# RF.net
KiCad netlist of a schematic drawn in Altium Designer
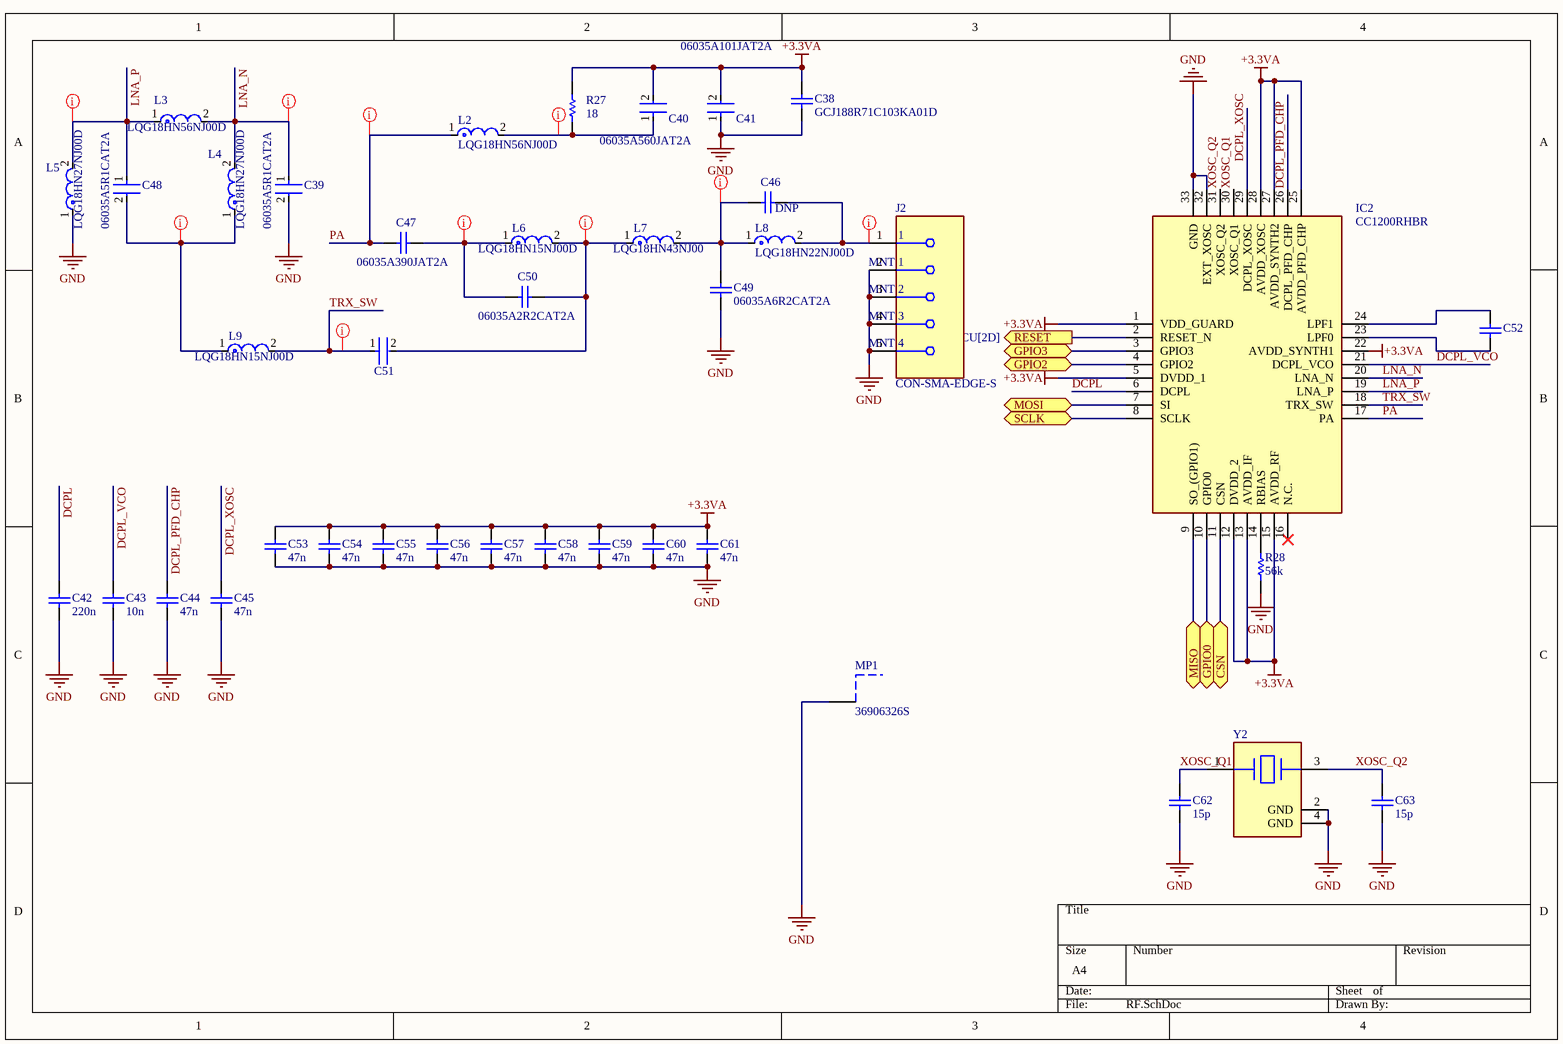
[diagram p0: RF.SchDoc]

(export (version "E")
  (design (tool "Eeschema 10.0.6"))
  (components
    (comp (ref "C38")
      (value "GCJ188R71C103KA01D")
      (footprint "CAPC1608X90X35LL10T15")
      (description "Cap Ceramic 0.01uF 16V X7R 10% Pad SMD 0603 Soft Termination 125C Automotive T/R")
      (fields (field (name "MANUFACTURER") "Murata"))
      (libsource (lib "Altium Content Vault") (part "CAP-NP-2"))
    )
    (comp (ref "C39")
      (value "06035A5R1CAT2A")
      (footprint "FP-GCM188-0_1-IPC_A")
      (description "0603 5.1 pF 50 V ±0.25 pF Tolerance C0G/NP0 Multilayer Ceramic Capacitor")
      (libsource (lib "Altium Content Vault") (part "02cd4be3c70576c341d710602a673aa"))
    )
    (comp (ref "C40")
      (value "06035A560JAT2A")
      (footprint "FP-GCM188-0_1-IPC_A")
      (description "0603 56 pF 50 V ±5% Tolerance C0G/NP0 Surface Mount Multilayer Ceramic Capacitor")
      (libsource (lib "Altium Content Vault") (part "02cd4be3c70576c341d710602a673aa"))
    )
    (comp (ref "C41")
      (value "06035A101JAT2A")
      (footprint "FP-GCM188-0_1-IPC_A")
      (description "0603 100 pF 50 V ±5% Tolerance C0G/NP0 SMT Multilayer Ceramic Capacitor")
      (libsource (lib "Altium Content Vault") (part "02cd4be3c70576c341d710602a673aa"))
    )
    (comp (ref "C42")
      (value "220n")
      (footprint "RES_0805")
      (description "Capacitor")
      (libsource (lib "Simulation Generic Components") (part "Capacitor"))
    )
    (comp (ref "C43")
      (value "10n")
      (footprint "RES_0805")
      (description "Capacitor")
      (libsource (lib "Simulation Generic Components") (part "Capacitor"))
    )
    (comp (ref "C44")
      (value "47n")
      (footprint "RES_0805")
      (description "Capacitor")
      (libsource (lib "Simulation Generic Components") (part "Capacitor"))
    )
    (comp (ref "C45")
      (value "47n")
      (footprint "RES_0805")
      (description "Capacitor")
      (libsource (lib "Simulation Generic Components") (part "Capacitor"))
    )
    (comp (ref "C46")
      (value "DNP")
      (footprint "CAPC1608X90X35LL15T15")
      (fields
        (field (name "PART NUMBER") "06035A6R2CAT2A")
        (field (name "MANUFACTURER") "AVX Interconnect / Elco")
      )
      (libsource (lib "Altium Content Vault") (part "CAP"))
    )
    (comp (ref "C47")
      (value "06035A390JAT2A")
      (footprint "CAPC1608X90X35LL15T15")
      (fields
        (field (name "PART NUMBER") "06035A6R2CAT2A")
        (field (name "MANUFACTURER") "AVX Interconnect / Elco")
      )
      (libsource (lib "Altium Content Vault") (part "CAP"))
    )
    (comp (ref "C48")
      (value "06035A5R1CAT2A")
      (footprint "FP-GCM188-0_1-IPC_A")
      (description "0603 5.1 pF 50 V ±0.25 pF Tolerance C0G/NP0 Multilayer Ceramic Capacitor")
      (libsource (lib "Altium Content Vault") (part "02cd4be3c70576c341d710602a673aa"))
    )
    (comp (ref "C49")
      (value "06035A6R2CAT2A")
      (footprint "CAPC1608X90X35LL15T15")
      (fields (field (name "MANUFACTURER") "AVX Interconnect / Elco"))
      (libsource (lib "Altium Content Vault") (part "CAP"))
    )
    (comp (ref "C50")
      (value "06035A2R2CAT2A")
      (footprint "CAPC1608X90X35LL15T15")
      (description "0603 2.2 pF 50 V ±0.25 pF Tolerance C0G/NP0 SMT Multilayer Ceramic Capacitor")
      (fields
        (field (name "PART NUMBER") "06035A6R2CAT2A")
        (field (name "MANUFACTURER") "AVX Interconnect / Elco")
      )
      (libsource (lib "Altium Content Vault") (part "CAP"))
    )
    (comp (ref "C51")
      (value "06035A5R1CAT2A")
      (footprint "FP-GCM188-0_1-IPC_A")
      (description "0603 5.1 pF 50 V ±0.25 pF Tolerance C0G/NP0 Multilayer Ceramic Capacitor")
      (libsource (lib "Altium Content Vault") (part "02cd4be3c70576c341d710602a673aa"))
    )
    (comp (ref "C52")
      (value "GCM188R71H152KA37D")
      (footprint "CAPC1608X90X35LL10T15")
      (fields (field (name "MANUFACTURER") "Murata"))
      (libsource (lib "Altium Content Vault") (part "CAP"))
    )
    (comp (ref "C53")
      (value "47n")
      (footprint "RES_0805")
      (description "Capacitor")
      (libsource (lib "Simulation Generic Components") (part "Capacitor"))
    )
    (comp (ref "C54")
      (value "47n")
      (footprint "RES_0805")
      (description "Capacitor")
      (libsource (lib "Simulation Generic Components") (part "Capacitor"))
    )
    (comp (ref "C55")
      (value "47n")
      (footprint "RES_0805")
      (description "Capacitor")
      (libsource (lib "Simulation Generic Components") (part "Capacitor"))
    )
    (comp (ref "C56")
      (value "47n")
      (footprint "RES_0805")
      (description "Capacitor")
      (libsource (lib "Simulation Generic Components") (part "Capacitor"))
    )
    (comp (ref "C57")
      (value "47n")
      (footprint "RES_0805")
      (description "Capacitor")
      (libsource (lib "Simulation Generic Components") (part "Capacitor"))
    )
    (comp (ref "C58")
      (value "47n")
      (footprint "RES_0805")
      (description "Capacitor")
      (libsource (lib "Simulation Generic Components") (part "Capacitor"))
    )
    (comp (ref "C59")
      (value "47n")
      (footprint "RES_0805")
      (description "Capacitor")
      (libsource (lib "Simulation Generic Components") (part "Capacitor"))
    )
    (comp (ref "C60")
      (value "47n")
      (footprint "RES_0805")
      (description "Capacitor")
      (libsource (lib "Simulation Generic Components") (part "Capacitor"))
    )
    (comp (ref "C61")
      (value "47n")
      (footprint "RES_0805")
      (description "Capacitor")
      (libsource (lib "Simulation Generic Components") (part "Capacitor"))
    )
    (comp (ref "C62")
      (value "15p")
      (footprint "RES_0805")
      (description "Capacitor")
      (libsource (lib "Simulation Generic Components") (part "Capacitor"))
    )
    (comp (ref "C63")
      (value "15p")
      (footprint "RES_0805")
      (description "Capacitor")
      (libsource (lib "Simulation Generic Components") (part "Capacitor"))
    )
    (comp (ref "IC2")
      (value "CC1200RHBR")
      (footprint "SamacSys:QFN50P500X500X100-33N-D")
      (description "Integrated Circuit")
      (fields (field (name "MOUSER PART NUMBER") "595-CC1200RHBR"))
      (libsource (lib "SamacSys") (part "CC1200RHBR"))
    )
    (comp (ref "J2")
      (value "CON-SMA-EDGE-S")
      (footprint "FP-CON-SMA-EDGE-S-MFG")
      (description "CONN SMA JACK STR EDGE MNT")
      (fields
        (field (name "OCTOPART") "https://octopart.com/con-sma-edge-s-rf+solutions-70967450")
        (field (name "MANUFACTURER") "RF Solutions Ltd.")
      )
      (libsource (lib "Altium Content Vault") (part "a163d97a771fcdd2fd1f1a9264c171f"))
    )
    (comp (ref "L2")
      (value "LQG18HN56NJ00D")
      (footprint "FP-LQG18HH_00-IPC_A")
      (description "Multilayer type RF Inductor 56nH ±5% 0.75Ω 400mA 0603")
      (fields (field (name "TOLERANCE") "5%"))
      (libsource (lib "Altium Content Vault") (part "4cc4b267dca4c8e51f7102f422741d8"))
    )
    (comp (ref "L3")
      (value "LQG18HN56NJ00D")
      (footprint "FP-LQG18HH_00-IPC_A")
      (description "Multilayer type RF Inductor 56nH ±5% 0.75Ω 400mA 0603")
      (fields (field (name "TOLERANCE") "5%"))
      (libsource (lib "Altium Content Vault") (part "4cc4b267dca4c8e51f7102f422741d8"))
    )
    (comp (ref "L4")
      (value "LQG18HN27NJ00D")
      (footprint "FP-LQG18HH_00-MFG")
      (description "Multilayer type RF Inductor 27nH ±5% 0.54Ω 500mA 0603")
      (fields (field (name "TOLERANCE") "5%"))
      (libsource (lib "Altium Content Vault") (part "4cc4b267dca4c8e51f7102f422741d8"))
    )
    (comp (ref "L5")
      (value "LQG18HN27NJ00D")
      (footprint "FP-LQG18HH_00-MFG")
      (description "Multilayer type RF Inductor 27nH ±5% 0.54Ω 500mA 0603")
      (fields (field (name "TOLERANCE") "5%"))
      (libsource (lib "Altium Content Vault") (part "4cc4b267dca4c8e51f7102f422741d8"))
    )
    (comp (ref "L6")
      (value "LQG18HN15NJ00D")
      (footprint "FP-LQG18HH_00-IPC_C")
      (description "Multilayer type RF Inductor 15nH ±5% 0.35Ω 600mA 0603")
      (fields (field (name "TOLERANCE") "5%"))
      (libsource (lib "Altium Content Vault") (part "4cc4b267dca4c8e51f7102f422741d8"))
    )
    (comp (ref "L7")
      (value "LQG18HN43NJ00")
      (footprint "FP-LQG18HH_00-IPC_C")
      (description "Multilayer type RF Inductor 43nH ±5%0603")
      (fields (field (name "TOLERANCE") "5%"))
      (libsource (lib "Altium Content Vault") (part "4cc4b267dca4c8e51f7102f422741d8"))
    )
    (comp (ref "L8")
      (value "LQG18HN22NJ00D")
      (footprint "FP-LQG18HH_00-IPC_C")
      (description "Multilayer type RF Inductor 22nH ±5% 0.5Ω 500mA 0603")
      (fields (field (name "TOLERANCE") "5%"))
      (libsource (lib "Altium Content Vault") (part "4cc4b267dca4c8e51f7102f422741d8"))
    )
    (comp (ref "L9")
      (value "LQG18HN15NJ00D")
      (footprint "FP-LQG18HH_00-IPC_C")
      (description "Multilayer type RF Inductor 15nH ±5% 0.35Ω 600mA 0603")
      (fields (field (name "TOLERANCE") "5%"))
      (libsource (lib "Altium Content Vault") (part "4cc4b267dca4c8e51f7102f422741d8"))
    )
    (comp (ref "MP1")
      (value "36906326S")
      (footprint "36906326S")
      (description "36906326S WE-SHC Shielding Cabinet")
      (libsource (lib "Altium Content Vault") (part "WE-SHC"))
    )
    (comp (ref "R27")
      (value "18")
      (footprint "RES_0805")
      (description "Resistor")
      (libsource (lib "Simulation Generic Components") (part "Resistor"))
    )
    (comp (ref "R28")
      (value "56k")
      (footprint "RES_0805")
      (description "Resistor")
      (libsource (lib "Simulation Generic Components") (part "Resistor"))
    )
    (comp (ref "Y2")
      (value "NX3225SA-40.000MHZ-STD-CSR-1 NDK")
      (footprint "FP-ABM8G-MFG")
      (description "Parallel - Fundamental Quartz Crystal, 40MHz Nom")
      (fields (field (name "TOLERANCE") "20ppm"))
      (libsource (lib "Altium Content Vault") (part "48e526d86b7f2615d98721063c72f49"))
    )
  )
  (nets
    (net (code "1") (name "+3.3VA") (class "Default")
      (node (ref "C38") (pin "2") (pinfunction "2_2") (pintype "passive"))
      (node (ref "C40") (pin "2") (pinfunction "2_2") (pintype "passive"))
      (node (ref "C41") (pin "2") (pinfunction "2_2") (pintype "passive"))
      (node (ref "C53") (pin "1") (pinfunction "1_1") (pintype "passive"))
      (node (ref "C54") (pin "1") (pinfunction "1_1") (pintype "passive"))
      (node (ref "C55") (pin "1") (pinfunction "1_1") (pintype "passive"))
      (node (ref "C56") (pin "1") (pinfunction "1_1") (pintype "passive"))
      (node (ref "C57") (pin "1") (pinfunction "1_1") (pintype "passive"))
      (node (ref "C58") (pin "1") (pinfunction "1_1") (pintype "passive"))
      (node (ref "C59") (pin "1") (pinfunction "1_1") (pintype "passive"))
      (node (ref "C60") (pin "1") (pinfunction "1_1") (pintype "passive"))
      (node (ref "C61") (pin "1") (pinfunction "1_1") (pintype "passive"))
      (node (ref "IC2") (pin "1") (pinfunction "VDD_GUARD_1") (pintype "passive"))
      (node (ref "IC2") (pin "12") (pinfunction "DVDD_2_12") (pintype "passive"))
      (node (ref "IC2") (pin "13") (pinfunction "AVDD_IF_13") (pintype "passive"))
      (node (ref "IC2") (pin "15") (pinfunction "AVDD_RF_15") (pintype "passive"))
      (node (ref "IC2") (pin "22") (pinfunction "AVDD_SYNTH1_22") (pintype "passive"))
      (node (ref "IC2") (pin "25") (pinfunction "AVDD_PFD_CHP_25") (pintype "passive"))
      (node (ref "IC2") (pin "27") (pinfunction "AVDD_SYNTH2_27") (pintype "passive"))
      (node (ref "IC2") (pin "28") (pinfunction "AVDD_XOSC_28") (pintype "passive"))
      (node (ref "IC2") (pin "5") (pinfunction "DVDD_1_5") (pintype "passive"))
      (node (ref "R27") (pin "1") (pinfunction "1_1") (pintype "passive"))
    )
    (net (code "2") (name "/CSN") (class "Default")
      (node (ref "IC2") (pin "11") (pinfunction "CSN_11") (pintype "passive"))
    )
    (net (code "3") (name "/DCPL") (class "Default")
      (node (ref "C42") (pin "1") (pinfunction "1_1") (pintype "passive"))
      (node (ref "IC2") (pin "6") (pinfunction "DCPL_6") (pintype "passive"))
    )
    (net (code "4") (name "/DCPL_PFD_CHP") (class "Default")
      (node (ref "C44") (pin "1") (pinfunction "1_1") (pintype "passive"))
      (node (ref "IC2") (pin "26") (pinfunction "DCPL_PFD_CHP_26") (pintype "passive"))
    )
    (net (code "5") (name "/DCPL_VCO") (class "Default")
      (node (ref "C43") (pin "1") (pinfunction "1_1") (pintype "passive"))
      (node (ref "IC2") (pin "21") (pinfunction "DCPL_VCO_21") (pintype "passive"))
    )
    (net (code "6") (name "/DCPL_XOSC") (class "Default")
      (node (ref "C45") (pin "1") (pinfunction "1_1") (pintype "passive"))
      (node (ref "IC2") (pin "29") (pinfunction "DCPL_XOSC_29") (pintype "passive"))
    )
    (net (code "7") (name "/GPIO0") (class "Default")
      (node (ref "IC2") (pin "10") (pinfunction "GPIO0_10") (pintype "passive"))
    )
    (net (code "8") (name "/GPIO2") (class "Default")
      (node (ref "IC2") (pin "4") (pinfunction "GPIO2_4") (pintype "passive"))
    )
    (net (code "9") (name "/GPIO3") (class "Default")
      (node (ref "IC2") (pin "3") (pinfunction "GPIO3_3") (pintype "passive"))
    )
    (net (code "10") (name "/LNA_N") (class "Default")
      (node (ref "C39") (pin "1") (pinfunction "1_1") (pintype "passive"))
      (node (ref "IC2") (pin "20") (pinfunction "LNA_N_20") (pintype "passive"))
      (node (ref "L3") (pin "2") (pinfunction "2_2") (pintype "passive"))
      (node (ref "L4") (pin "2") (pinfunction "2_2") (pintype "passive"))
    )
    (net (code "11") (name "/LNA_P") (class "Default")
      (node (ref "C48") (pin "1") (pinfunction "1_1") (pintype "passive"))
      (node (ref "IC2") (pin "19") (pinfunction "LNA_P_19") (pintype "passive"))
      (node (ref "L3") (pin "1") (pinfunction "1_1") (pintype "passive"))
      (node (ref "L5") (pin "2") (pinfunction "2_2") (pintype "passive"))
    )
    (net (code "12") (name "/MISO") (class "Default")
      (node (ref "IC2") (pin "9") (pinfunction "SO_(GPIO1)_9") (pintype "passive"))
    )
    (net (code "13") (name "/MOSI") (class "Default")
      (node (ref "IC2") (pin "7") (pinfunction "SI_7") (pintype "passive"))
    )
    (net (code "14") (name "/PA") (class "Default")
      (node (ref "C47") (pin "2") (pinfunction "2_2") (pintype "passive"))
      (node (ref "IC2") (pin "17") (pinfunction "PA_17") (pintype "passive"))
      (node (ref "L2") (pin "1") (pinfunction "1_1") (pintype "passive"))
    )
    (net (code "15") (name "/RESET") (class "Default")
      (node (ref "IC2") (pin "2") (pinfunction "RESET_N_2") (pintype "passive"))
    )
    (net (code "16") (name "/SCLK") (class "Default")
      (node (ref "IC2") (pin "8") (pinfunction "SCLK_8") (pintype "passive"))
    )
    (net (code "17") (name "/TRX_SW") (class "Default")
      (node (ref "C51") (pin "1") (pinfunction "1_1") (pintype "passive"))
      (node (ref "IC2") (pin "18") (pinfunction "TRX_SW_18") (pintype "passive"))
      (node (ref "L9") (pin "2") (pinfunction "2_2") (pintype "passive"))
    )
    (net (code "18") (name "/XOSC_Q1") (class "Default")
      (node (ref "C62") (pin "1") (pinfunction "1_1") (pintype "passive"))
      (node (ref "IC2") (pin "30") (pinfunction "XOSC_Q1_30") (pintype "passive"))
      (node (ref "Y2") (pin "1") (pinfunction "1_1") (pintype "passive"))
    )
    (net (code "19") (name "/XOSC_Q2") (class "Default")
      (node (ref "C63") (pin "1") (pinfunction "1_1") (pintype "passive"))
      (node (ref "IC2") (pin "31") (pinfunction "XOSC_Q2_31") (pintype "passive"))
      (node (ref "Y2") (pin "3") (pinfunction "3_3") (pintype "passive"))
    )
    (net (code "20") (name "GND") (class "Default")
      (node (ref "C38") (pin "1") (pinfunction "1_1") (pintype "passive"))
      (node (ref "C39") (pin "2") (pinfunction "2_2") (pintype "passive"))
      (node (ref "C41") (pin "1") (pinfunction "1_1") (pintype "passive"))
      (node (ref "C42") (pin "2") (pinfunction "2_2") (pintype "passive"))
      (node (ref "C43") (pin "2") (pinfunction "2_2") (pintype "passive"))
      (node (ref "C44") (pin "2") (pinfunction "2_2") (pintype "passive"))
      (node (ref "C45") (pin "2") (pinfunction "2_2") (pintype "passive"))
      (node (ref "C49") (pin "1") (pinfunction "1_1") (pintype "passive"))
      (node (ref "C53") (pin "2") (pinfunction "2_2") (pintype "passive"))
      (node (ref "C54") (pin "2") (pinfunction "2_2") (pintype "passive"))
      (node (ref "C55") (pin "2") (pinfunction "2_2") (pintype "passive"))
      (node (ref "C56") (pin "2") (pinfunction "2_2") (pintype "passive"))
      (node (ref "C57") (pin "2") (pinfunction "2_2") (pintype "passive"))
      (node (ref "C58") (pin "2") (pinfunction "2_2") (pintype "passive"))
      (node (ref "C59") (pin "2") (pinfunction "2_2") (pintype "passive"))
      (node (ref "C60") (pin "2") (pinfunction "2_2") (pintype "passive"))
      (node (ref "C61") (pin "2") (pinfunction "2_2") (pintype "passive"))
      (node (ref "C62") (pin "2") (pinfunction "2_2") (pintype "passive"))
      (node (ref "C63") (pin "2") (pinfunction "2_2") (pintype "passive"))
      (node (ref "IC2") (pin "32") (pinfunction "EXT_XOSC_32") (pintype "passive"))
      (node (ref "IC2") (pin "33") (pinfunction "GND_33") (pintype "passive"))
      (node (ref "J2") (pin "2") (pinfunction "MNT_1_2") (pintype "passive"))
      (node (ref "J2") (pin "3") (pinfunction "MNT_2_3") (pintype "passive"))
      (node (ref "J2") (pin "4") (pinfunction "MNT_3_4") (pintype "passive"))
      (node (ref "J2") (pin "5") (pinfunction "MNT_4_5") (pintype "passive"))
      (node (ref "L5") (pin "1") (pinfunction "1_1") (pintype "passive"))
      (node (ref "MP1") (pin "1") (pinfunction "1_1") (pintype "passive"))
      (node (ref "R28") (pin "2") (pinfunction "2_2") (pintype "passive"))
      (node (ref "Y2") (pin "2") (pinfunction "GND_2") (pintype "power_in"))
      (node (ref "Y2") (pin "4") (pinfunction "GND_4") (pintype "power_in"))
    )
    (net (code "21") (name "Net-(C40-Pad1)") (class "Default")
      (node (ref "C40") (pin "1") (pinfunction "1_1") (pintype "passive"))
      (node (ref "L2") (pin "2") (pinfunction "2_2") (pintype "passive"))
      (node (ref "R27") (pin "2") (pinfunction "2_2") (pintype "passive"))
    )
    (net (code "22") (name "Net-(C46-Pad1)") (class "Default")
      (node (ref "C46") (pin "1") (pinfunction "1_1") (pintype "passive"))
      (node (ref "J2") (pin "1") (pinfunction "1_1") (pintype "passive"))
      (node (ref "L8") (pin "2") (pinfunction "2_2") (pintype "passive"))
    )
    (net (code "23") (name "Net-(C46-Pad2)") (class "Default")
      (node (ref "C46") (pin "2") (pinfunction "2_2") (pintype "passive"))
      (node (ref "C49") (pin "2") (pinfunction "2_2") (pintype "passive"))
      (node (ref "L7") (pin "2") (pinfunction "2_2") (pintype "passive"))
      (node (ref "L8") (pin "1") (pinfunction "1_1") (pintype "passive"))
    )
    (net (code "24") (name "Net-(C47-Pad1)") (class "Default")
      (node (ref "C47") (pin "1") (pinfunction "1_1") (pintype "passive"))
      (node (ref "C50") (pin "2") (pinfunction "2_2") (pintype "passive"))
      (node (ref "L6") (pin "1") (pinfunction "1_1") (pintype "passive"))
    )
    (net (code "25") (name "Net-(C48-Pad2)") (class "Default")
      (node (ref "C48") (pin "2") (pinfunction "2_2") (pintype "passive"))
      (node (ref "L4") (pin "1") (pinfunction "1_1") (pintype "passive"))
      (node (ref "L9") (pin "1") (pinfunction "1_1") (pintype "passive"))
    )
    (net (code "26") (name "Net-(C50-Pad1)") (class "Default")
      (node (ref "C50") (pin "1") (pinfunction "1_1") (pintype "passive"))
      (node (ref "C51") (pin "2") (pinfunction "2_2") (pintype "passive"))
      (node (ref "L6") (pin "2") (pinfunction "2_2") (pintype "passive"))
      (node (ref "L7") (pin "1") (pinfunction "1_1") (pintype "passive"))
    )
    (net (code "27") (name "Net-(IC2-LPF0)") (class "Default")
      (node (ref "C52") (pin "1") (pinfunction "1_1") (pintype "passive"))
      (node (ref "IC2") (pin "23") (pinfunction "LPF0_23") (pintype "passive"))
    )
    (net (code "28") (name "Net-(IC2-LPF1)") (class "Default")
      (node (ref "C52") (pin "2") (pinfunction "2_2") (pintype "passive"))
      (node (ref "IC2") (pin "24") (pinfunction "LPF1_24") (pintype "passive"))
    )
    (net (code "29") (name "Net-(IC2-RBIAS)") (class "Default")
      (node (ref "IC2") (pin "14") (pinfunction "RBIAS_14") (pintype "passive"))
      (node (ref "R28") (pin "1") (pinfunction "1_1") (pintype "passive"))
    )
    (net (code "30") (name "unconnected-(IC2-N.C.-Pad16)") (class "Default")
      (node (ref "IC2") (pin "16") (pinfunction "N.C._16") (pintype "passive+no_connect"))
    )
  )
)
